# FMC_connector.net
KiCad netlist of a schematic drawn in Altium Designer
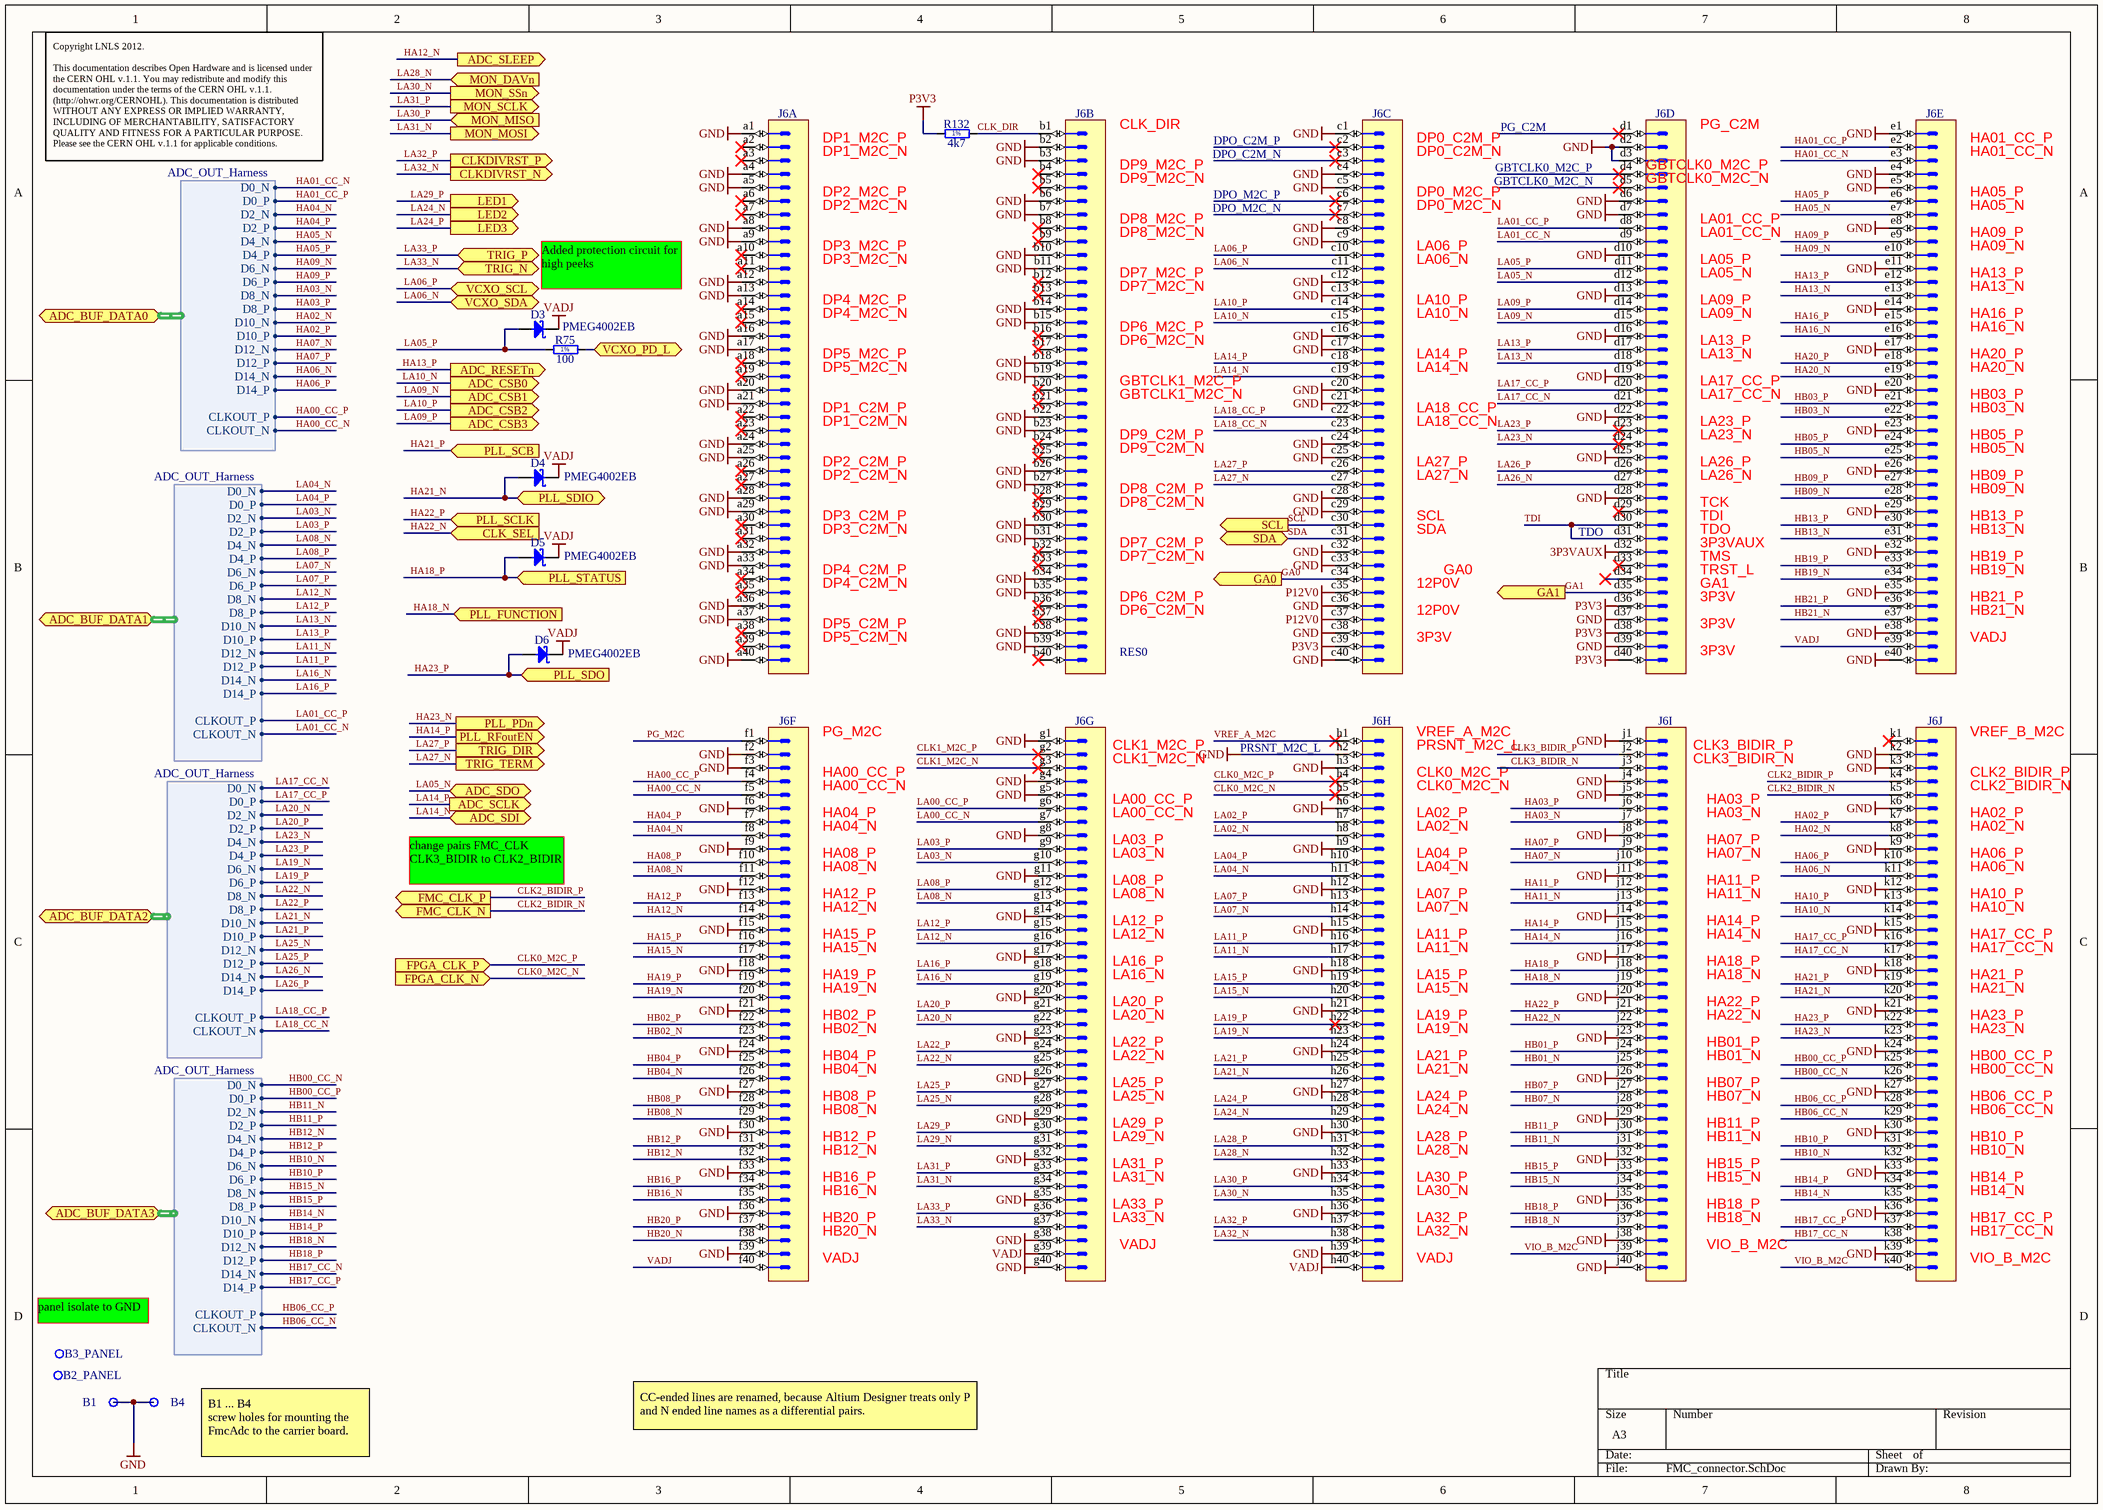
[diagram p0: FMC_connector.SchDoc]

(export (version "E")
  (design (tool "Eeschema 10.0.6"))
  (components
    (comp (ref "B1")
      (value "Plated Hole")
      (footprint "MTG270_500_M")
      (description "Single Terminal Socket")
      (fields (field (name "PART NUMBER") "PLATED_HOLE2.7_PAD5.0_M") (field (name "AUTHOR") "LNLS DIG FCS"))
      (libsource (lib "Eletro-mechanical_LNLS") (part "Single Terminal Socket"))
    )
    (comp (ref "B2_PANEL")
      (value "Plated Hole")
      (footprint "MTG270_500_M")
      (description "Single Terminal Socket")
      (fields (field (name "PART NUMBER") "PLATED_HOLE2.7_PAD5.0_M") (field (name "AUTHOR") "LNLS DIG FCS"))
      (libsource (lib "Eletro-mechanical_LNLS") (part "Single Terminal Socket"))
    )
    (comp (ref "B3_PANEL")
      (value "Plated Hole")
      (footprint "MTG270_500_M")
      (description "Single Terminal Socket")
      (fields (field (name "PART NUMBER") "PLATED_HOLE2.7_PAD5.0_M") (field (name "AUTHOR") "LNLS DIG FCS"))
      (libsource (lib "Eletro-mechanical_LNLS") (part "Single Terminal Socket"))
    )
    (comp (ref "B4")
      (value "Plated Hole")
      (footprint "MTG270_500_M")
      (description "Single Terminal Socket")
      (fields (field (name "PART NUMBER") "PLATED_HOLE2.7_PAD5.0_M") (field (name "AUTHOR") "LNLS DIG FCS"))
      (libsource (lib "Eletro-mechanical_LNLS") (part "Single Terminal Socket"))
    )
    (comp (ref "D3")
      (value "PMEG4002EB")
      (footprint "SODFL1608X65N")
      (description "Schottky Diode")
      (fields
        (field (name "VOLTAGE") "40V")
        (field (name "POWER") "200mA")
        (field (name "AUTHOR") "CERN DEM JMW")
      )
      (libsource (lib "ICs And Semiconductors") (part "Diode Schottky"))
    )
    (comp (ref "D4")
      (value "PMEG4002EB")
      (footprint "SODFL1608X65N")
      (description "Schottky Diode")
      (fields
        (field (name "VOLTAGE") "40V")
        (field (name "POWER") "200mA")
        (field (name "AUTHOR") "CERN DEM JMW")
      )
      (libsource (lib "ICs And Semiconductors") (part "Diode Schottky"))
    )
    (comp (ref "D5")
      (value "PMEG4002EB")
      (footprint "SODFL1608X65N")
      (description "Schottky Diode")
      (fields
        (field (name "VOLTAGE") "40V")
        (field (name "POWER") "200mA")
        (field (name "AUTHOR") "CERN DEM JMW")
      )
      (libsource (lib "ICs And Semiconductors") (part "Diode Schottky"))
    )
    (comp (ref "D6")
      (value "PMEG4002EB")
      (footprint "SODFL1608X65N")
      (description "Schottky Diode")
      (fields
        (field (name "VOLTAGE") "40V")
        (field (name "POWER") "200mA")
        (field (name "AUTHOR") "CERN DEM JMW")
      )
      (libsource (lib "ICs And Semiconductors") (part "Diode Schottky"))
    )
    (comp (ref "J6")
      (value "~")
      (footprint "SAMTEC_ASP-134488-01")
      (description "Connector VITA 57, 400 Male contacts in 10 row abcdefghj")
      (fields
        (field (name "PART NUMBER") "SAMTEC_ASP-134488-01")
        (field (name "MANUFACTURER") "SAMTEC")
        (field (name "AUTHOR") "CERN DEM JLC")
      )
      (libsource (lib "Connectors") (part "Connector VITA 57 400 Male (abcdefghjk)"))
    )
    (comp (ref "R75")
      (value "100")
      (footprint "RESC1005X40N")
      (description "Resistor - 1%")
      (fields
        (field (name "PART NUMBER") "R0402_100R_1%_0.0625W_100PPM")
        (field (name "POWER") "0.0625W")
        (field (name "AUTHOR") "CERN DEM JLC")
      )
      (libsource (lib "Resistors") (part "Resistor - 1%"))
    )
    (comp (ref "R132")
      (value "4k7")
      (footprint "RESC1005X40N")
      (description "Resistor - 1%")
      (fields
        (field (name "PART NUMBER") "R0402_4K7_1%_0.0625W_100PPM")
        (field (name "POWER") "0.0625W")
        (field (name "AUTHOR") "CERN DEM JLC")
      )
      (libsource (lib "Resistors") (part "Resistor - 1%"))
    )
  )
  (nets
    (net (code "2") (name "/CLK0_M2C_N") (class "Default")
      (node (ref "J6") (pin "h5") (pinfunction "h5_h5") (pintype "bidirectional+no_connect"))
    )
    (net (code "3") (name "/CLK0_M2C_P") (class "Default")
      (node (ref "J6") (pin "h4") (pinfunction "h4_h4") (pintype "bidirectional+no_connect"))
    )
    (net (code "4") (name "/CLK1_M2C_N") (class "Default")
      (node (ref "J6") (pin "g3") (pinfunction "g3_g3") (pintype "bidirectional+no_connect"))
    )
    (net (code "5") (name "/CLK1_M2C_P") (class "Default")
      (node (ref "J6") (pin "g2") (pinfunction "g2_g2") (pintype "bidirectional+no_connect"))
    )
    (net (code "6") (name "/CLK2_BIDIR_N") (class "Default")
      (node (ref "J6") (pin "k5") (pinfunction "k5_k5") (pintype "bidirectional"))
    )
    (net (code "7") (name "/CLK2_BIDIR_P") (class "Default")
      (node (ref "J6") (pin "k4") (pinfunction "k4_k4") (pintype "bidirectional"))
    )
    (net (code "8") (name "/CLK3_BIDIR_N") (class "Default")
      (node (ref "J6") (pin "j3") (pinfunction "j3_j3") (pintype "bidirectional"))
    )
    (net (code "9") (name "/CLK3_BIDIR_P") (class "Default")
      (node (ref "J6") (pin "j2") (pinfunction "j2_j2") (pintype "bidirectional"))
    )
    (net (code "10") (name "/CLK_DIR") (class "Default")
      (node (ref "J6") (pin "b1") (pinfunction "b1_b1") (pintype "bidirectional"))
      (node (ref "R132") (pin "2") (pinfunction "2_2") (pintype "passive"))
    )
    (net (code "11") (name "/GA0") (class "Default")
      (node (ref "J6") (pin "c34") (pinfunction "c34_c34") (pintype "bidirectional"))
    )
    (net (code "12") (name "/GA1") (class "Default")
      (node (ref "J6") (pin "d35") (pinfunction "d35_d35") (pintype "bidirectional"))
    )
    (net (code "13") (name "/HA00_CC_N") (class "Default")
      (node (ref "J6") (pin "f5") (pinfunction "f5_f5") (pintype "bidirectional"))
    )
    (net (code "14") (name "/HA00_CC_P") (class "Default")
      (node (ref "J6") (pin "f4") (pinfunction "f4_f4") (pintype "bidirectional"))
    )
    (net (code "15") (name "/HA01_CC_N") (class "Default")
      (node (ref "J6") (pin "e3") (pinfunction "e3_e3") (pintype "bidirectional"))
    )
    (net (code "16") (name "/HA01_CC_P") (class "Default")
      (node (ref "J6") (pin "e2") (pinfunction "e2_e2") (pintype "bidirectional"))
    )
    (net (code "17") (name "/HA02_N") (class "Default")
      (node (ref "J6") (pin "k8") (pinfunction "k8_k8") (pintype "bidirectional"))
    )
    (net (code "18") (name "/HA02_P") (class "Default")
      (node (ref "J6") (pin "k7") (pinfunction "k7_k7") (pintype "bidirectional"))
    )
    (net (code "19") (name "/HA03_N") (class "Default")
      (node (ref "J6") (pin "j7") (pinfunction "j7_j7") (pintype "bidirectional"))
    )
    (net (code "20") (name "/HA03_P") (class "Default")
      (node (ref "J6") (pin "j6") (pinfunction "j6_j6") (pintype "bidirectional"))
    )
    (net (code "21") (name "/HA04_N") (class "Default")
      (node (ref "J6") (pin "f8") (pinfunction "f8_f8") (pintype "bidirectional"))
    )
    (net (code "22") (name "/HA04_P") (class "Default")
      (node (ref "J6") (pin "f7") (pinfunction "f7_f7") (pintype "bidirectional"))
    )
    (net (code "23") (name "/HA05_N") (class "Default")
      (node (ref "J6") (pin "e7") (pinfunction "e7_e7") (pintype "bidirectional"))
    )
    (net (code "24") (name "/HA05_P") (class "Default")
      (node (ref "J6") (pin "e6") (pinfunction "e6_e6") (pintype "bidirectional"))
    )
    (net (code "25") (name "/HA06_N") (class "Default")
      (node (ref "J6") (pin "k11") (pinfunction "k11_k11") (pintype "bidirectional"))
    )
    (net (code "26") (name "/HA06_P") (class "Default")
      (node (ref "J6") (pin "k10") (pinfunction "k10_k10") (pintype "bidirectional"))
    )
    (net (code "27") (name "/HA07_N") (class "Default")
      (node (ref "J6") (pin "j10") (pinfunction "j10_j10") (pintype "bidirectional"))
    )
    (net (code "28") (name "/HA07_P") (class "Default")
      (node (ref "J6") (pin "j9") (pinfunction "j9_j9") (pintype "bidirectional"))
    )
    (net (code "29") (name "/HA08_N") (class "Default")
      (node (ref "J6") (pin "f11") (pinfunction "f11_f11") (pintype "bidirectional"))
    )
    (net (code "30") (name "/HA08_P") (class "Default")
      (node (ref "J6") (pin "f10") (pinfunction "f10_f10") (pintype "bidirectional"))
    )
    (net (code "31") (name "/HA09_N") (class "Default")
      (node (ref "J6") (pin "e10") (pinfunction "e10_e10") (pintype "bidirectional"))
    )
    (net (code "32") (name "/HA09_P") (class "Default")
      (node (ref "J6") (pin "e9") (pinfunction "e9_e9") (pintype "bidirectional"))
    )
    (net (code "33") (name "/HA10_N") (class "Default")
      (node (ref "J6") (pin "k14") (pinfunction "k14_k14") (pintype "bidirectional"))
    )
    (net (code "34") (name "/HA10_P") (class "Default")
      (node (ref "J6") (pin "k13") (pinfunction "k13_k13") (pintype "bidirectional"))
    )
    (net (code "35") (name "/HA11_N") (class "Default")
      (node (ref "J6") (pin "j13") (pinfunction "j13_j13") (pintype "bidirectional"))
    )
    (net (code "36") (name "/HA11_P") (class "Default")
      (node (ref "J6") (pin "j12") (pinfunction "j12_j12") (pintype "bidirectional"))
    )
    (net (code "37") (name "/HA12_N") (class "Default")
      (node (ref "J6") (pin "f14") (pinfunction "f14_f14") (pintype "bidirectional"))
    )
    (net (code "38") (name "/HA12_P") (class "Default")
      (node (ref "J6") (pin "f13") (pinfunction "f13_f13") (pintype "bidirectional"))
    )
    (net (code "39") (name "/HA13_N") (class "Default")
      (node (ref "J6") (pin "e13") (pinfunction "e13_e13") (pintype "bidirectional"))
    )
    (net (code "40") (name "/HA13_P") (class "Default")
      (node (ref "J6") (pin "e12") (pinfunction "e12_e12") (pintype "bidirectional"))
    )
    (net (code "41") (name "/HA14_N") (class "Default")
      (node (ref "J6") (pin "j16") (pinfunction "j16_j16") (pintype "bidirectional"))
    )
    (net (code "42") (name "/HA14_P") (class "Default")
      (node (ref "J6") (pin "j15") (pinfunction "j15_j15") (pintype "bidirectional"))
    )
    (net (code "43") (name "/HA15_N") (class "Default")
      (node (ref "J6") (pin "f17") (pinfunction "f17_f17") (pintype "bidirectional"))
    )
    (net (code "44") (name "/HA15_P") (class "Default")
      (node (ref "J6") (pin "f16") (pinfunction "f16_f16") (pintype "bidirectional"))
    )
    (net (code "45") (name "/HA16_N") (class "Default")
      (node (ref "J6") (pin "e16") (pinfunction "e16_e16") (pintype "bidirectional"))
    )
    (net (code "46") (name "/HA16_P") (class "Default")
      (node (ref "J6") (pin "e15") (pinfunction "e15_e15") (pintype "bidirectional"))
    )
    (net (code "47") (name "/HA17_CC_N") (class "Default")
      (node (ref "J6") (pin "k17") (pinfunction "k17_k17") (pintype "bidirectional"))
    )
    (net (code "48") (name "/HA17_CC_P") (class "Default")
      (node (ref "J6") (pin "k16") (pinfunction "k16_k16") (pintype "bidirectional"))
    )
    (net (code "49") (name "/HA18_N") (class "Default")
      (node (ref "J6") (pin "j19") (pinfunction "j19_j19") (pintype "bidirectional"))
    )
    (net (code "50") (name "/HA18_P") (class "Default")
      (node (ref "D5") (pin "2") (pinfunction "A_2") (pintype "passive"))
      (node (ref "J6") (pin "j18") (pinfunction "j18_j18") (pintype "bidirectional"))
    )
    (net (code "51") (name "/HA19_N") (class "Default")
      (node (ref "J6") (pin "f20") (pinfunction "f20_f20") (pintype "bidirectional"))
    )
    (net (code "52") (name "/HA19_P") (class "Default")
      (node (ref "J6") (pin "f19") (pinfunction "f19_f19") (pintype "bidirectional"))
    )
    (net (code "53") (name "/HA20_N") (class "Default")
      (node (ref "J6") (pin "e19") (pinfunction "e19_e19") (pintype "bidirectional"))
    )
    (net (code "54") (name "/HA20_P") (class "Default")
      (node (ref "J6") (pin "e18") (pinfunction "e18_e18") (pintype "bidirectional"))
    )
    (net (code "55") (name "/HA21_N") (class "Default")
      (node (ref "D4") (pin "2") (pinfunction "A_2") (pintype "passive"))
      (node (ref "J6") (pin "k20") (pinfunction "k20_k20") (pintype "bidirectional"))
    )
    (net (code "56") (name "/HA21_P") (class "Default")
      (node (ref "J6") (pin "k19") (pinfunction "k19_k19") (pintype "bidirectional"))
    )
    (net (code "57") (name "/HA22_N") (class "Default")
      (node (ref "J6") (pin "j22") (pinfunction "j22_j22") (pintype "bidirectional"))
    )
    (net (code "58") (name "/HA22_P") (class "Default")
      (node (ref "J6") (pin "j21") (pinfunction "j21_j21") (pintype "bidirectional"))
    )
    (net (code "59") (name "/HA23_N") (class "Default")
      (node (ref "J6") (pin "k23") (pinfunction "k23_k23") (pintype "bidirectional"))
    )
    (net (code "60") (name "/HA23_P") (class "Default")
      (node (ref "D6") (pin "2") (pinfunction "A_2") (pintype "passive"))
      (node (ref "J6") (pin "k22") (pinfunction "k22_k22") (pintype "bidirectional"))
    )
    (net (code "61") (name "/HB00_CC_N") (class "Default")
      (node (ref "J6") (pin "k26") (pinfunction "k26_k26") (pintype "bidirectional"))
    )
    (net (code "62") (name "/HB00_CC_P") (class "Default")
      (node (ref "J6") (pin "k25") (pinfunction "k25_k25") (pintype "bidirectional"))
    )
    (net (code "63") (name "/HB01_N") (class "Default")
      (node (ref "J6") (pin "j25") (pinfunction "j25_j25") (pintype "bidirectional"))
    )
    (net (code "64") (name "/HB01_P") (class "Default")
      (node (ref "J6") (pin "j24") (pinfunction "j24_j24") (pintype "bidirectional"))
    )
    (net (code "65") (name "/HB02_N") (class "Default")
      (node (ref "J6") (pin "f23") (pinfunction "f23_f23") (pintype "bidirectional"))
    )
    (net (code "66") (name "/HB02_P") (class "Default")
      (node (ref "J6") (pin "f22") (pinfunction "f22_f22") (pintype "bidirectional"))
    )
    (net (code "67") (name "/HB03_N") (class "Default")
      (node (ref "J6") (pin "e22") (pinfunction "e22_e22") (pintype "bidirectional"))
    )
    (net (code "68") (name "/HB03_P") (class "Default")
      (node (ref "J6") (pin "e21") (pinfunction "e21_e21") (pintype "bidirectional"))
    )
    (net (code "69") (name "/HB04_N") (class "Default")
      (node (ref "J6") (pin "f26") (pinfunction "f26_f26") (pintype "bidirectional"))
    )
    (net (code "70") (name "/HB04_P") (class "Default")
      (node (ref "J6") (pin "f25") (pinfunction "f25_f25") (pintype "bidirectional"))
    )
    (net (code "71") (name "/HB05_N") (class "Default")
      (node (ref "J6") (pin "e25") (pinfunction "e25_e25") (pintype "bidirectional"))
    )
    (net (code "72") (name "/HB05_P") (class "Default")
      (node (ref "J6") (pin "e24") (pinfunction "e24_e24") (pintype "bidirectional"))
    )
    (net (code "73") (name "/HB06_CC_N") (class "Default")
      (node (ref "J6") (pin "k29") (pinfunction "k29_k29") (pintype "bidirectional"))
    )
    (net (code "74") (name "/HB06_CC_P") (class "Default")
      (node (ref "J6") (pin "k28") (pinfunction "k28_k28") (pintype "bidirectional"))
    )
    (net (code "75") (name "/HB07_N") (class "Default")
      (node (ref "J6") (pin "j28") (pinfunction "j28_j28") (pintype "bidirectional"))
    )
    (net (code "76") (name "/HB07_P") (class "Default")
      (node (ref "J6") (pin "j27") (pinfunction "j27_j27") (pintype "bidirectional"))
    )
    (net (code "77") (name "/HB08_N") (class "Default")
      (node (ref "J6") (pin "f29") (pinfunction "f29_f29") (pintype "bidirectional"))
    )
    (net (code "78") (name "/HB08_P") (class "Default")
      (node (ref "J6") (pin "f28") (pinfunction "f28_f28") (pintype "bidirectional"))
    )
    (net (code "79") (name "/HB09_N") (class "Default")
      (node (ref "J6") (pin "e28") (pinfunction "e28_e28") (pintype "bidirectional"))
    )
    (net (code "80") (name "/HB09_P") (class "Default")
      (node (ref "J6") (pin "e27") (pinfunction "e27_e27") (pintype "bidirectional"))
    )
    (net (code "81") (name "/HB10_N") (class "Default")
      (node (ref "J6") (pin "k32") (pinfunction "k32_k32") (pintype "bidirectional"))
    )
    (net (code "82") (name "/HB10_P") (class "Default")
      (node (ref "J6") (pin "k31") (pinfunction "k31_k31") (pintype "bidirectional"))
    )
    (net (code "83") (name "/HB11_N") (class "Default")
      (node (ref "J6") (pin "j31") (pinfunction "j31_j31") (pintype "bidirectional"))
    )
    (net (code "84") (name "/HB11_P") (class "Default")
      (node (ref "J6") (pin "j30") (pinfunction "j30_j30") (pintype "bidirectional"))
    )
    (net (code "85") (name "/HB12_N") (class "Default")
      (node (ref "J6") (pin "f32") (pinfunction "f32_f32") (pintype "bidirectional"))
    )
    (net (code "86") (name "/HB12_P") (class "Default")
      (node (ref "J6") (pin "f31") (pinfunction "f31_f31") (pintype "bidirectional"))
    )
    (net (code "87") (name "/HB13_N") (class "Default")
      (node (ref "J6") (pin "e31") (pinfunction "e31_e31") (pintype "bidirectional"))
    )
    (net (code "88") (name "/HB13_P") (class "Default")
      (node (ref "J6") (pin "e30") (pinfunction "e30_e30") (pintype "bidirectional"))
    )
    (net (code "89") (name "/HB14_N") (class "Default")
      (node (ref "J6") (pin "k35") (pinfunction "k35_k35") (pintype "bidirectional"))
    )
    (net (code "90") (name "/HB14_P") (class "Default")
      (node (ref "J6") (pin "k34") (pinfunction "k34_k34") (pintype "bidirectional"))
    )
    (net (code "91") (name "/HB15_N") (class "Default")
      (node (ref "J6") (pin "j34") (pinfunction "j34_j34") (pintype "bidirectional"))
    )
    (net (code "92") (name "/HB15_P") (class "Default")
      (node (ref "J6") (pin "j33") (pinfunction "j33_j33") (pintype "bidirectional"))
    )
    (net (code "93") (name "/HB16_N") (class "Default")
      (node (ref "J6") (pin "f35") (pinfunction "f35_f35") (pintype "bidirectional"))
    )
    (net (code "94") (name "/HB16_P") (class "Default")
      (node (ref "J6") (pin "f34") (pinfunction "f34_f34") (pintype "bidirectional"))
    )
    (net (code "95") (name "/HB17_CC_N") (class "Default")
      (node (ref "J6") (pin "k38") (pinfunction "k38_k38") (pintype "bidirectional"))
    )
    (net (code "96") (name "/HB17_CC_P") (class "Default")
      (node (ref "J6") (pin "k37") (pinfunction "k37_k37") (pintype "bidirectional"))
    )
    (net (code "97") (name "/HB18_N") (class "Default")
      (node (ref "J6") (pin "j37") (pinfunction "j37_j37") (pintype "bidirectional"))
    )
    (net (code "98") (name "/HB18_P") (class "Default")
      (node (ref "J6") (pin "j36") (pinfunction "j36_j36") (pintype "bidirectional"))
    )
    (net (code "99") (name "/HB19_N") (class "Default")
      (node (ref "J6") (pin "e34") (pinfunction "e34_e34") (pintype "bidirectional"))
    )
    (net (code "100") (name "/HB19_P") (class "Default")
      (node (ref "J6") (pin "e33") (pinfunction "e33_e33") (pintype "bidirectional"))
    )
    (net (code "101") (name "/HB20_N") (class "Default")
      (node (ref "J6") (pin "f38") (pinfunction "f38_f38") (pintype "bidirectional"))
    )
    (net (code "102") (name "/HB20_P") (class "Default")
      (node (ref "J6") (pin "f37") (pinfunction "f37_f37") (pintype "bidirectional"))
    )
    (net (code "103") (name "/HB21_N") (class "Default")
      (node (ref "J6") (pin "e37") (pinfunction "e37_e37") (pintype "bidirectional"))
    )
    (net (code "104") (name "/HB21_P") (class "Default")
      (node (ref "J6") (pin "e36") (pinfunction "e36_e36") (pintype "bidirectional"))
    )
    (net (code "105") (name "/LA00_CC_N") (class "Default")
      (node (ref "J6") (pin "g7") (pinfunction "g7_g7") (pintype "bidirectional"))
    )
    (net (code "106") (name "/LA00_CC_P") (class "Default")
      (node (ref "J6") (pin "g6") (pinfunction "g6_g6") (pintype "bidirectional"))
    )
    (net (code "107") (name "/LA01_CC_N") (class "Default")
      (node (ref "J6") (pin "d9") (pinfunction "d9_d9") (pintype "bidirectional"))
    )
    (net (code "108") (name "/LA01_CC_P") (class "Default")
      (node (ref "J6") (pin "d8") (pinfunction "d8_d8") (pintype "bidirectional"))
    )
    (net (code "109") (name "/LA02_N") (class "Default")
      (node (ref "J6") (pin "h8") (pinfunction "h8_h8") (pintype "bidirectional"))
    )
    (net (code "110") (name "/LA02_P") (class "Default")
      (node (ref "J6") (pin "h7") (pinfunction "h7_h7") (pintype "bidirectional"))
    )
    (net (code "111") (name "/LA03_N") (class "Default")
      (node (ref "J6") (pin "g10") (pinfunction "g10_g10") (pintype "bidirectional"))
    )
    (net (code "112") (name "/LA03_P") (class "Default")
      (node (ref "J6") (pin "g9") (pinfunction "g9_g9") (pintype "bidirectional"))
    )
    (net (code "113") (name "/LA04_N") (class "Default")
      (node (ref "J6") (pin "h11") (pinfunction "h11_h11") (pintype "bidirectional"))
    )
    (net (code "114") (name "/LA04_P") (class "Default")
      (node (ref "J6") (pin "h10") (pinfunction "h10_h10") (pintype "bidirectional"))
    )
    (net (code "115") (name "/LA05_N") (class "Default")
      (node (ref "J6") (pin "d12") (pinfunction "d12_d12") (pintype "bidirectional"))
    )
    (net (code "116") (name "/LA05_P") (class "Default")
      (node (ref "D3") (pin "2") (pinfunction "A_2") (pintype "passive"))
      (node (ref "J6") (pin "d11") (pinfunction "d11_d11") (pintype "bidirectional"))
      (node (ref "R75") (pin "1") (pinfunction "1_1") (pintype "passive"))
    )
    (net (code "117") (name "/LA06_N") (class "Default")
      (node (ref "J6") (pin "c11") (pinfunction "c11_c11") (pintype "bidirectional"))
    )
    (net (code "118") (name "/LA06_P") (class "Default")
      (node (ref "J6") (pin "c10") (pinfunction "c10_c10") (pintype "bidirectional"))
    )
    (net (code "119") (name "/LA07_N") (class "Default")
      (node (ref "J6") (pin "h14") (pinfunction "h14_h14") (pintype "bidirectional"))
    )
    (net (code "120") (name "/LA07_P") (class "Default")
      (node (ref "J6") (pin "h13") (pinfunction "h13_h13") (pintype "bidirectional"))
    )
    (net (code "121") (name "/LA08_N") (class "Default")
      (node (ref "J6") (pin "g13") (pinfunction "g13_g13") (pintype "bidirectional"))
    )
    (net (code "122") (name "/LA08_P") (class "Default")
      (node (ref "J6") (pin "g12") (pinfunction "g12_g12") (pintype "bidirectional"))
    )
    (net (code "123") (name "/LA09_N") (class "Default")
      (node (ref "J6") (pin "d15") (pinfunction "d15_d15") (pintype "bidirectional"))
    )
    (net (code "124") (name "/LA09_P") (class "Default")
      (node (ref "J6") (pin "d14") (pinfunction "d14_d14") (pintype "bidirectional"))
    )
    (net (code "125") (name "/LA10_N") (class "Default")
      (node (ref "J6") (pin "c15") (pinfunction "c15_c15") (pintype "bidirectional"))
    )
    (net (code "126") (name "/LA10_P") (class "Default")
      (node (ref "J6") (pin "c14") (pinfunction "c14_c14") (pintype "bidirectional"))
    )
    (net (code "127") (name "/LA11_N") (class "Default")
      (node (ref "J6") (pin "h17") (pinfunction "h17_h17") (pintype "bidirectional"))
    )
    (net (code "128") (name "/LA11_P") (class "Default")
      (node (ref "J6") (pin "h16") (pinfunction "h16_h16") (pintype "bidirectional"))
    )
    (net (code "129") (name "/LA12_N") (class "Default")
      (node (ref "J6") (pin "g16") (pinfunction "g16_g16") (pintype "bidirectional"))
    )
    (net (code "130") (name "/LA12_P") (class "Default")
      (node (ref "J6") (pin "g15") (pinfunction "g15_g15") (pintype "bidirectional"))
    )
    (net (code "131") (name "/LA13_N") (class "Default")
      (node (ref "J6") (pin "d18") (pinfunction "d18_d18") (pintype "bidirectional"))
    )
    (net (code "132") (name "/LA13_P") (class "Default")
      (node (ref "J6") (pin "d17") (pinfunction "d17_d17") (pintype "bidirectional"))
    )
    (net (code "133") (name "/LA14_N") (class "Default")
      (node (ref "J6") (pin "c19") (pinfunction "c19_c19") (pintype "bidirectional"))
    )
    (net (code "134") (name "/LA14_P") (class "Default")
      (node (ref "J6") (pin "c18") (pinfunction "c18_c18") (pintype "bidirectional"))
    )
    (net (code "135") (name "/LA15_N") (class "Default")
      (node (ref "J6") (pin "h20") (pinfunction "h20_h20") (pintype "bidirectional"))
    )
    (net (code "136") (name "/LA15_P") (class "Default")
      (node (ref "J6") (pin "h19") (pinfunction "h19_h19") (pintype "bidirectional"))
    )
    (net (code "137") (name "/LA16_N") (class "Default")
      (node (ref "J6") (pin "g19") (pinfunction "g19_g19") (pintype "bidirectional"))
    )
    (net (code "138") (name "/LA16_P") (class "Default")
      (node (ref "J6") (pin "g18") (pinfunction "g18_g18") (pintype "bidirectional"))
    )
    (net (code "139") (name "/LA17_CC_N") (class "Default")
      (node (ref "J6") (pin "d21") (pinfunction "d21_d21") (pintype "bidirectional"))
    )
    (net (code "140") (name "/LA17_CC_P") (class "Default")
      (node (ref "J6") (pin "d20") (pinfunction "d20_d20") (pintype "bidirectional"))
    )
    (net (code "141") (name "/LA18_CC_N") (class "Default")
      (node (ref "J6") (pin "c23") (pinfunction "c23_c23") (pintype "bidirectional"))
    )
    (net (code "142") (name "/LA18_CC_P") (class "Default")
      (node (ref "J6") (pin "c22") (pinfunction "c22_c22") (pintype "bidirectional"))
    )
    (net (code "143") (name "/LA19_N") (class "Default")
      (node (ref "J6") (pin "h23") (pinfunction "h23_h23") (pintype "bidirectional"))
    )
    (net (code "144") (name "/LA19_P") (class "Default")
      (node (ref "J6") (pin "h22") (pinfunction "h22_h22") (pintype "bidirectional+no_connect"))
    )
    (net (code "145") (name "/LA20_N") (class "Default")
      (node (ref "J6") (pin "g22") (pinfunction "g22_g22") (pintype "bidirectional"))
    )
    (net (code "146") (name "/LA20_P") (class "Default")
      (node (ref "J6") (pin "g21") (pinfunction "g21_g21") (pintype "bidirectional"))
    )
    (net (code "147") (name "/LA21_N") (class "Default")
      (node (ref "J6") (pin "h26") (pinfunction "h26_h26") (pintype "bidirectional"))
    )
    (net (code "148") (name "/LA21_P") (class "Default")
      (node (ref "J6") (pin "h25") (pinfunction "h25_h25") (pintype "bidirectional"))
    )
    (net (code "149") (name "/LA22_N") (class "Default")
      (node (ref "J6") (pin "g25") (pinfunction "g25_g25") (pintype "bidirectional"))
    )
    (net (code "150") (name "/LA22_P") (class "Default")
      (node (ref "J6") (pin "g24") (pinfunction "g24_g24") (pintype "bidirectional"))
    )
    (net (code "151") (name "/LA23_N") (class "Default")
      (node (ref "J6") (pin "d24") (pinfunction "d24_d24") (pintype "bidirectional"))
    )
    (net (code "152") (name "/LA23_P") (class "Default")
      (node (ref "J6") (pin "d23") (pinfunction "d23_d23") (pintype "bidirectional"))
    )
    (net (code "153") (name "/LA24_N") (class "Default")
      (node (ref "J6") (pin "h29") (pinfunction "h29_h29") (pintype "bidirectional"))
    )
    (net (code "154") (name "/LA24_P") (class "Default")
      (node (ref "J6") (pin "h28") (pinfunction "h28_h28") (pintype "bidirectional"))
    )
    (net (code "155") (name "/LA25_N") (class "Default")
      (node (ref "J6") (pin "g28") (pinfunction "g28_g28") (pintype "bidirectional"))
    )
    (net (code "156") (name "/LA25_P") (class "Default")
      (node (ref "J6") (pin "g27") (pinfunction "g27_g27") (pintype "bidirectional"))
    )
    (net (code "157") (name "/LA26_N") (class "Default")
      (node (ref "J6") (pin "d27") (pinfunction "d27_d27") (pintype "bidirectional"))
    )
    (net (code "158") (name "/LA26_P") (class "Default")
      (node (ref "J6") (pin "d26") (pinfunction "d26_d26") (pintype "bidirectional"))
    )
    (net (code "159") (name "/LA27_N") (class "Default")
      (node (ref "J6") (pin "c27") (pinfunction "c27_c27") (pintype "bidirectional"))
    )
    (net (code "160") (name "/LA27_P") (class "Default")
      (node (ref "J6") (pin "c26") (pinfunction "c26_c26") (pintype "bidirectional"))
    )
    (net (code "161") (name "/LA28_N") (class "Default")
      (node (ref "J6") (pin "h32") (pinfunction "h32_h32") (pintype "bidirectional"))
    )
    (net (code "162") (name "/LA28_P") (class "Default")
      (node (ref "J6") (pin "h31") (pinfunction "h31_h31") (pintype "bidirectional"))
    )
    (net (code "163") (name "/LA29_N") (class "Default")
      (node (ref "J6") (pin "g31") (pinfunction "g31_g31") (pintype "bidirectional"))
    )
    (net (code "164") (name "/LA29_P") (class "Default")
      (node (ref "J6") (pin "g30") (pinfunction "g30_g30") (pintype "bidirectional"))
    )
    (net (code "165") (name "/LA30_N") (class "Default")
      (node (ref "J6") (pin "h35") (pinfunction "h35_h35") (pintype "bidirectional"))
    )
    (net (code "166") (name "/LA30_P") (class "Default")
      (node (ref "J6") (pin "h34") (pinfunction "h34_h34") (pintype "bidirectional"))
    )
    (net (code "167") (name "/LA31_N") (class "Default")
      (node (ref "J6") (pin "g34") (pinfunction "g34_g34") (pintype "bidirectional"))
    )
    (net (code "168") (name "/LA31_P") (class "Default")
      (node (ref "J6") (pin "g33") (pinfunction "g33_g33") (pintype "bidirectional"))
    )
    (net (code "169") (name "/LA32_N") (class "Default")
      (node (ref "J6") (pin "h38") (pinfunction "h38_h38") (pintype "bidirectional"))
    )
    (net (code "170") (name "/LA32_P") (class "Default")
      (node (ref "J6") (pin "h37") (pinfunction "h37_h37") (pintype "bidirectional"))
    )
    (net (code "171") (name "/LA33_N") (class "Default")
      (node (ref "J6") (pin "g37") (pinfunction "g37_g37") (pintype "bidirectional"))
    )
    (net (code "172") (name "/LA33_P") (class "Default")
      (node (ref "J6") (pin "g36") (pinfunction "g36_g36") (pintype "bidirectional"))
    )
    (net (code "173") (name "/PG_M2C") (class "Default")
      (node (ref "J6") (pin "f1") (pinfunction "f1_f1") (pintype "bidirectional"))
    )
    (net (code "174") (name "/SCL") (class "Default")
      (node (ref "J6") (pin "c30") (pinfunction "c30_c30") (pintype "bidirectional"))
    )
    (net (code "175") (name "/SDA") (class "Default")
      (node (ref "J6") (pin "c31") (pinfunction "c31_c31") (pintype "bidirectional"))
    )
    (net (code "176") (name "/TDI") (class "Default")
      (node (ref "J6") (pin "d30") (pinfunction "d30_d30") (pintype "bidirectional"))
      (node (ref "J6") (pin "d31") (pinfunction "d31_d31") (pintype "bidirectional"))
    )
    (net (code "177") (name "/VCXO_PD_L") (class "Default")
      (node (ref "R75") (pin "2") (pinfunction "2_2") (pintype "passive"))
    )
    (net (code "178") (name "/VIO_B_M2C") (class "Default")
      (node (ref "J6") (pin "j39") (pinfunction "j39_j39") (pintype "bidirectional"))
      (node (ref "J6") (pin "k40") (pinfunction "k40_k40") (pintype "bidirectional"))
    )
    (net (code "179") (name "/VREF_A_M2C") (class "Default")
      (node (ref "J6") (pin "h1") (pinfunction "h1_h1") (pintype "bidirectional+no_connect"))
    )
    (net (code "181") (name "3P3VAUX") (class "Default")
      (node (ref "J6") (pin "d32") (pinfunction "d32_d32") (pintype "bidirectional"))
    )
    (net (code "182") (name "GND") (class "Default")
      (node (ref "B1") (pin "1") (pinfunction "1_1") (pintype "bidirectional"))
      (node (ref "B4") (pin "1") (pinfunction "1_1") (pintype "bidirectional"))
      (node (ref "J6") (pin "a1") (pinfunction "a1_a1") (pintype "bidirectional"))
      (node (ref "J6") (pin "a12") (pinfunction "a12_a12") (pintype "bidirectional"))
      (node (ref "J6") (pin "a13") (pinfunction "a13_a13") (pintype "bidirectional"))
      (node (ref "J6") (pin "a16") (pinfunction "a16_a16") (pintype "bidirectional"))
      (node (ref "J6") (pin "a17") (pinfunction "a17_a17") (pintype "bidirectional"))
      (node (ref "J6") (pin "a20") (pinfunction "a20_a20") (pintype "bidirectional"))
      (node (ref "J6") (pin "a21") (pinfunction "a21_a21") (pintype "bidirectional"))
      (node (ref "J6") (pin "a24") (pinfunction "a24_a24") (pintype "bidirectional"))
      (node (ref "J6") (pin "a25") (pinfunction "a25_a25") (pintype "bidirectional"))
      (node (ref "J6") (pin "a28") (pinfunction "a28_a28") (pintype "bidirectional"))
      (node (ref "J6") (pin "a29") (pinfunction "a29_a29") (pintype "bidirectional"))
      (node (ref "J6") (pin "a32") (pinfunction "a32_a32") (pintype "bidirectional"))
      (node (ref "J6") (pin "a33") (pinfunction "a33_a33") (pintype "bidirectional"))
      (node (ref "J6") (pin "a36") (pinfunction "a36_a36") (pintype "bidirectional"))
      (node (ref "J6") (pin "a37") (pinfunction "a37_a37") (pintype "bidirectional"))
      (node (ref "J6") (pin "a4") (pinfunction "a4_a4") (pintype "bidirectional"))
      (node (ref "J6") (pin "a40") (pinfunction "a40_a40") (pintype "bidirectional"))
      (node (ref "J6") (pin "a5") (pinfunction "a5_a5") (pintype "bidirectional"))
      (node (ref "J6") (pin "a8") (pinfunction "a8_a8") (pintype "bidirectional"))
      (node (ref "J6") (pin "a9") (pinfunction "a9_a9") (pintype "bidirectional"))
      (node (ref "J6") (pin "b10") (pinfunction "b10_b10") (pintype "bidirectional"))
      (node (ref "J6") (pin "b11") (pinfunction "b11_b11") (pintype "bidirectional"))
      (node (ref "J6") (pin "b14") (pinfunction "b14_b14") (pintype "bidirectional"))
      (node (ref "J6") (pin "b15") (pinfunction "b15_b15") (pintype "bidirectional"))
      (node (ref "J6") (pin "b18") (pinfunction "b18_b18") (pintype "bidirectional"))
      (node (ref "J6") (pin "b19") (pinfunction "b19_b19") (pintype "bidirectional"))
      (node (ref "J6") (pin "b2") (pinfunction "b2_b2") (pintype "bidirectional"))
      (node (ref "J6") (pin "b22") (pinfunction "b22_b22") (pintype "bidirectional"))
      (node (ref "J6") (pin "b23") (pinfunction "b23_b23") (pintype "bidirectional"))
      (node (ref "J6") (pin "b26") (pinfunction "b26_b26") (pintype "bidirectional"))
      (node (ref "J6") (pin "b27") (pinfunction "b27_b27") (pintype "bidirectional"))
      (node (ref "J6") (pin "b3") (pinfunction "b3_b3") (pintype "bidirectional"))
      (node (ref "J6") (pin "b30") (pinfunction "b30_b30") (pintype "bidirectional"))
      (node (ref "J6") (pin "b31") (pinfunction "b31_b31") (pintype "bidirectional"))
      (node (ref "J6") (pin "b34") (pinfunction "b34_b34") (pintype "bidirectional"))
      (node (ref "J6") (pin "b35") (pinfunction "b35_b35") (pintype "bidirectional"))
      (node (ref "J6") (pin "b38") (pinfunction "b38_b38") (pintype "bidirectional"))
      (node (ref "J6") (pin "b39") (pinfunction "b39_b39") (pintype "bidirectional"))
      (node (ref "J6") (pin "b6") (pinfunction "b6_b6") (pintype "bidirectional"))
      (node (ref "J6") (pin "b7") (pinfunction "b7_b7") (pintype "bidirectional"))
      (node (ref "J6") (pin "c1") (pinfunction "c1_c1") (pintype "bidirectional"))
      (node (ref "J6") (pin "c12") (pinfunction "c12_c12") (pintype "bidirectional"))
      (node (ref "J6") (pin "c13") (pinfunction "c13_c13") (pintype "bidirectional"))
      (node (ref "J6") (pin "c16") (pinfunction "c16_c16") (pintype "bidirectional"))
      (node (ref "J6") (pin "c17") (pinfunction "c17_c17") (pintype "bidirectional"))
      (node (ref "J6") (pin "c20") (pinfunction "c20_c20") (pintype "bidirectional"))
      (node (ref "J6") (pin "c21") (pinfunction "c21_c21") (pintype "bidirectional"))
      (node (ref "J6") (pin "c24") (pinfunction "c24_c24") (pintype "bidirectional"))
      (node (ref "J6") (pin "c25") (pinfunction "c25_c25") (pintype "bidirectional"))
      (node (ref "J6") (pin "c28") (pinfunction "c28_c28") (pintype "bidirectional"))
      (node (ref "J6") (pin "c29") (pinfunction "c29_c29") (pintype "bidirectional"))
      (node (ref "J6") (pin "c32") (pinfunction "c32_c32") (pintype "bidirectional"))
      (node (ref "J6") (pin "c33") (pinfunction "c33_c33") (pintype "bidirectional"))
      (node (ref "J6") (pin "c36") (pinfunction "c36_c36") (pintype "bidirectional"))
      (node (ref "J6") (pin "c38") (pinfunction "c38_c38") (pintype "bidirectional"))
      (node (ref "J6") (pin "c4") (pinfunction "c4_c4") (pintype "bidirectional"))
      (node (ref "J6") (pin "c40") (pinfunction "c40_c40") (pintype "bidirectional"))
      (node (ref "J6") (pin "c5") (pinfunction "c5_c5") (pintype "bidirectional"))
      (node (ref "J6") (pin "c8") (pinfunction "c8_c8") (pintype "bidirectional"))
      (node (ref "J6") (pin "c9") (pinfunction "c9_c9") (pintype "bidirectional"))
      (node (ref "J6") (pin "d10") (pinfunction "d10_d10") (pintype "bidirectional"))
      (node (ref "J6") (pin "d13") (pinfunction "d13_d13") (pintype "bidirectional"))
      (node (ref "J6") (pin "d16") (pinfunction "d16_d16") (pintype "bidirectional"))
      (node (ref "J6") (pin "d19") (pinfunction "d19_d19") (pintype "bidirectional"))
      (node (ref "J6") (pin "d2") (pinfunction "d2_d2") (pintype "bidirectional"))
      (node (ref "J6") (pin "d22") (pinfunction "d22_d22") (pintype "bidirectional"))
      (node (ref "J6") (pin "d25") (pinfunction "d25_d25") (pintype "bidirectional"))
      (node (ref "J6") (pin "d28") (pinfunction "d28_d28") (pintype "bidirectional"))
      (node (ref "J6") (pin "d3") (pinfunction "d3_d3") (pintype "bidirectional"))
      (node (ref "J6") (pin "d37") (pinfunction "d37_d37") (pintype "bidirectional"))
      (node (ref "J6") (pin "d39") (pinfunction "d39_d39") (pintype "bidirectional"))
      (node (ref "J6") (pin "d6") (pinfunction "d6_d6") (pintype "bidirectional"))
      (node (ref "J6") (pin "d7") (pinfunction "d7_d7") (pintype "bidirectional"))
      (node (ref "J6") (pin "e1") (pinfunction "e1_e1") (pintype "bidirectional"))
      (node (ref "J6") (pin "e11") (pinfunction "e11_e11") (pintype "bidirectional"))
      (node (ref "J6") (pin "e14") (pinfunction "e14_e14") (pintype "bidirectional"))
      (node (ref "J6") (pin "e17") (pinfunction "e17_e17") (pintype "bidirectional"))
      (node (ref "J6") (pin "e20") (pinfunction "e20_e20") (pintype "bidirectional"))
      (node (ref "J6") (pin "e23") (pinfunction "e23_e23") (pintype "bidirectional"))
      (node (ref "J6") (pin "e26") (pinfunction "e26_e26") (pintype "bidirectional"))
      (node (ref "J6") (pin "e29") (pinfunction "e29_e29") (pintype "bidirectional"))
      (node (ref "J6") (pin "e32") (pinfunction "e32_e32") (pintype "bidirectional"))
      (node (ref "J6") (pin "e35") (pinfunction "e35_e35") (pintype "bidirectional"))
      (node (ref "J6") (pin "e38") (pinfunction "e38_e38") (pintype "bidirectional"))
      (node (ref "J6") (pin "e4") (pinfunction "e4_e4") (pintype "bidirectional"))
      (node (ref "J6") (pin "e40") (pinfunction "e40_e40") (pintype "bidirectional"))
      (node (ref "J6") (pin "e5") (pinfunction "e5_e5") (pintype "bidirectional"))
      (node (ref "J6") (pin "e8") (pinfunction "e8_e8") (pintype "bidirectional"))
      (node (ref "J6") (pin "f12") (pinfunction "f12_f12") (pintype "bidirectional"))
      (node (ref "J6") (pin "f15") (pinfunction "f15_f15") (pintype "bidirectional"))
      (node (ref "J6") (pin "f18") (pinfunction "f18_f18") (pintype "bidirectional"))
      (node (ref "J6") (pin "f2") (pinfunction "f2_f2") (pintype "bidirectional"))
      (node (ref "J6") (pin "f21") (pinfunction "f21_f21") (pintype "bidirectional"))
      (node (ref "J6") (pin "f24") (pinfunction "f24_f24") (pintype "bidirectional"))
      (node (ref "J6") (pin "f27") (pinfunction "f27_f27") (pintype "bidirectional"))
      (node (ref "J6") (pin "f3") (pinfunction "f3_f3") (pintype "bidirectional"))
      (node (ref "J6") (pin "f30") (pinfunction "f30_f30") (pintype "bidirectional"))
      (node (ref "J6") (pin "f33") (pinfunction "f33_f33") (pintype "bidirectional"))
      (node (ref "J6") (pin "f36") (pinfunction "f36_f36") (pintype "bidirectional"))
      (node (ref "J6") (pin "f39") (pinfunction "f39_f39") (pintype "bidirectional"))
      (node (ref "J6") (pin "f6") (pinfunction "f6_f6") (pintype "bidirectional"))
      (node (ref "J6") (pin "f9") (pinfunction "f9_f9") (pintype "bidirectional"))
      (node (ref "J6") (pin "g1") (pinfunction "g1_g1") (pintype "bidirectional"))
      (node (ref "J6") (pin "g11") (pinfunction "g11_g11") (pintype "bidirectional"))
      (node (ref "J6") (pin "g14") (pinfunction "g14_g14") (pintype "bidirectional"))
      (node (ref "J6") (pin "g17") (pinfunction "g17_g17") (pintype "bidirectional"))
      (node (ref "J6") (pin "g20") (pinfunction "g20_g20") (pintype "bidirectional"))
      (node (ref "J6") (pin "g23") (pinfunction "g23_g23") (pintype "bidirectional"))
      (node (ref "J6") (pin "g26") (pinfunction "g26_g26") (pintype "bidirectional"))
      (node (ref "J6") (pin "g29") (pinfunction "g29_g29") (pintype "bidirectional"))
      (node (ref "J6") (pin "g32") (pinfunction "g32_g32") (pintype "bidirectional"))
      (node (ref "J6") (pin "g35") (pinfunction "g35_g35") (pintype "bidirectional"))
      (node (ref "J6") (pin "g38") (pinfunction "g38_g38") (pintype "bidirectional"))
      (node (ref "J6") (pin "g4") (pinfunction "g4_g4") (pintype "bidirectional"))
      (node (ref "J6") (pin "g40") (pinfunction "g40_g40") (pintype "bidirectional"))
      (node (ref "J6") (pin "g5") (pinfunction "g5_g5") (pintype "bidirectional"))
      (node (ref "J6") (pin "g8") (pinfunction "g8_g8") (pintype "bidirectional"))
      (node (ref "J6") (pin "h12") (pinfunction "h12_h12") (pintype "bidirectional"))
      (node (ref "J6") (pin "h15") (pinfunction "h15_h15") (pintype "bidirectional"))
      (node (ref "J6") (pin "h18") (pinfunction "h18_h18") (pintype "bidirectional"))
      (node (ref "J6") (pin "h2") (pinfunction "h2_h2") (pintype "bidirectional"))
      (node (ref "J6") (pin "h21") (pinfunction "h21_h21") (pintype "bidirectional"))
      (node (ref "J6") (pin "h24") (pinfunction "h24_h24") (pintype "bidirectional"))
      (node (ref "J6") (pin "h27") (pinfunction "h27_h27") (pintype "bidirectional"))
      (node (ref "J6") (pin "h3") (pinfunction "h3_h3") (pintype "bidirectional"))
      (node (ref "J6") (pin "h30") (pinfunction "h30_h30") (pintype "bidirectional"))
      (node (ref "J6") (pin "h33") (pinfunction "h33_h33") (pintype "bidirectional"))
      (node (ref "J6") (pin "h36") (pinfunction "h36_h36") (pintype "bidirectional"))
      (node (ref "J6") (pin "h39") (pinfunction "h39_h39") (pintype "bidirectional"))
      (node (ref "J6") (pin "h6") (pinfunction "h6_h6") (pintype "bidirectional"))
      (node (ref "J6") (pin "h9") (pinfunction "h9_h9") (pintype "bidirectional"))
      (node (ref "J6") (pin "j1") (pinfunction "j1_j1") (pintype "bidirectional"))
      (node (ref "J6") (pin "j11") (pinfunction "j11_j11") (pintype "bidirectional"))
      (node (ref "J6") (pin "j14") (pinfunction "j14_j14") (pintype "bidirectional"))
      (node (ref "J6") (pin "j17") (pinfunction "j17_j17") (pintype "bidirectional"))
      (node (ref "J6") (pin "j20") (pinfunction "j20_j20") (pintype "bidirectional"))
      (node (ref "J6") (pin "j23") (pinfunction "j23_j23") (pintype "bidirectional"))
      (node (ref "J6") (pin "j26") (pinfunction "j26_j26") (pintype "bidirectional"))
      (node (ref "J6") (pin "j29") (pinfunction "j29_j29") (pintype "bidirectional"))
      (node (ref "J6") (pin "j32") (pinfunction "j32_j32") (pintype "bidirectional"))
      (node (ref "J6") (pin "j35") (pinfunction "j35_j35") (pintype "bidirectional"))
      (node (ref "J6") (pin "j38") (pinfunction "j38_j38") (pintype "bidirectional"))
      (node (ref "J6") (pin "j4") (pinfunction "j4_j4") (pintype "bidirectional"))
      (node (ref "J6") (pin "j40") (pinfunction "j40_j40") (pintype "bidirectional"))
      (node (ref "J6") (pin "j5") (pinfunction "j5_j5") (pintype "bidirectional"))
      (node (ref "J6") (pin "j8") (pinfunction "j8_j8") (pintype "bidirectional"))
      (node (ref "J6") (pin "k12") (pinfunction "k12_k12") (pintype "bidirectional"))
      (node (ref "J6") (pin "k15") (pinfunction "k15_k15") (pintype "bidirectional"))
      (node (ref "J6") (pin "k18") (pinfunction "k18_k18") (pintype "bidirectional"))
      (node (ref "J6") (pin "k2") (pinfunction "k2_k2") (pintype "bidirectional"))
      (node (ref "J6") (pin "k21") (pinfunction "k21_k21") (pintype "bidirectional"))
      (node (ref "J6") (pin "k24") (pinfunction "k24_k24") (pintype "bidirectional"))
      (node (ref "J6") (pin "k27") (pinfunction "k27_k27") (pintype "bidirectional"))
      (node (ref "J6") (pin "k3") (pinfunction "k3_k3") (pintype "bidirectional"))
      (node (ref "J6") (pin "k30") (pinfunction "k30_k30") (pintype "bidirectional"))
      (node (ref "J6") (pin "k33") (pinfunction "k33_k33") (pintype "bidirectional"))
      (node (ref "J6") (pin "k36") (pinfunction "k36_k36") (pintype "bidirectional"))
      (node (ref "J6") (pin "k39") (pinfunction "k39_k39") (pintype "bidirectional"))
      (node (ref "J6") (pin "k6") (pinfunction "k6_k6") (pintype "bidirectional"))
      (node (ref "J6") (pin "k9") (pinfunction "k9_k9") (pintype "bidirectional"))
    )
    (net (code "183") (name "P3V3") (class "Default")
      (node (ref "J6") (pin "c39") (pinfunction "c39_c39") (pintype "bidirectional"))
      (node (ref "J6") (pin "d36") (pinfunction "d36_d36") (pintype "bidirectional"))
      (node (ref "J6") (pin "d38") (pinfunction "d38_d38") (pintype "bidirectional"))
      (node (ref "J6") (pin "d40") (pinfunction "d40_d40") (pintype "bidirectional"))
      (node (ref "R132") (pin "1") (pinfunction "1_1") (pintype "passive"))
    )
    (net (code "184") (name "P12V0") (class "Default")
      (node (ref "J6") (pin "c35") (pinfunction "c35_c35") (pintype "bidirectional"))
      (node (ref "J6") (pin "c37") (pinfunction "c37_c37") (pintype "bidirectional"))
    )
    (net (code "185") (name "VADJ") (class "Default")
      (node (ref "D3") (pin "1") (pinfunction "C_1") (pintype "passive"))
      (node (ref "D4") (pin "1") (pinfunction "C_1") (pintype "passive"))
      (node (ref "D5") (pin "1") (pinfunction "C_1") (pintype "passive"))
      (node (ref "D6") (pin "1") (pinfunction "C_1") (pintype "passive"))
      (node (ref "J6") (pin "e39") (pinfunction "e39_e39") (pintype "bidirectional"))
      (node (ref "J6") (pin "f40") (pinfunction "f40_f40") (pintype "bidirectional"))
      (node (ref "J6") (pin "g39") (pinfunction "g39_g39") (pintype "bidirectional"))
      (node (ref "J6") (pin "h40") (pinfunction "h40_h40") (pintype "bidirectional"))
    )
    (net (code "186") (name "unconnected-(B2_PANEL-Pad1)") (class "Default")
      (node (ref "B2_PANEL") (pin "1") (pinfunction "1_1") (pintype "bidirectional"))
    )
    (net (code "187") (name "unconnected-(B3_PANEL-Pad1)") (class "Default")
      (node (ref "B3_PANEL") (pin "1") (pinfunction "1_1") (pintype "bidirectional"))
    )
    (net (code "188") (name "unconnected-(J6-Pada2)") (class "Default")
      (node (ref "J6") (pin "a2") (pinfunction "a2_a2") (pintype "bidirectional+no_connect"))
    )
    (net (code "189") (name "unconnected-(J6-Pada3)") (class "Default")
      (node (ref "J6") (pin "a3") (pinfunction "a3_a3") (pintype "bidirectional+no_connect"))
    )
    (net (code "190") (name "unconnected-(J6-Pada6)") (class "Default")
      (node (ref "J6") (pin "a6") (pinfunction "a6_a6") (pintype "bidirectional+no_connect"))
    )
    (net (code "191") (name "unconnected-(J6-Pada7)") (class "Default")
      (node (ref "J6") (pin "a7") (pinfunction "a7_a7") (pintype "bidirectional+no_connect"))
    )
    (net (code "192") (name "unconnected-(J6-Pada10)") (class "Default")
      (node (ref "J6") (pin "a10") (pinfunction "a10_a10") (pintype "bidirectional+no_connect"))
    )
    (net (code "193") (name "unconnected-(J6-Pada11)") (class "Default")
      (node (ref "J6") (pin "a11") (pinfunction "a11_a11") (pintype "bidirectional+no_connect"))
    )
    (net (code "194") (name "unconnected-(J6-Pada14)") (class "Default")
      (node (ref "J6") (pin "a14") (pinfunction "a14_a14") (pintype "bidirectional+no_connect"))
    )
    (net (code "195") (name "unconnected-(J6-Pada15)") (class "Default")
      (node (ref "J6") (pin "a15") (pinfunction "a15_a15") (pintype "bidirectional+no_connect"))
    )
    (net (code "196") (name "unconnected-(J6-Pada18)") (class "Default")
      (node (ref "J6") (pin "a18") (pinfunction "a18_a18") (pintype "bidirectional+no_connect"))
    )
    (net (code "197") (name "unconnected-(J6-Pada19)") (class "Default")
      (node (ref "J6") (pin "a19") (pinfunction "a19_a19") (pintype "bidirectional+no_connect"))
    )
    (net (code "198") (name "unconnected-(J6-Pada22)") (class "Default")
      (node (ref "J6") (pin "a22") (pinfunction "a22_a22") (pintype "bidirectional+no_connect"))
    )
    (net (code "199") (name "unconnected-(J6-Pada23)") (class "Default")
      (node (ref "J6") (pin "a23") (pinfunction "a23_a23") (pintype "bidirectional+no_connect"))
    )
    (net (code "200") (name "unconnected-(J6-Pada26)") (class "Default")
      (node (ref "J6") (pin "a26") (pinfunction "a26_a26") (pintype "bidirectional+no_connect"))
    )
    (net (code "201") (name "unconnected-(J6-Pada27)") (class "Default")
      (node (ref "J6") (pin "a27") (pinfunction "a27_a27") (pintype "bidirectional+no_connect"))
    )
    (net (code "202") (name "unconnected-(J6-Pada30)") (class "Default")
      (node (ref "J6") (pin "a30") (pinfunction "a30_a30") (pintype "bidirectional+no_connect"))
    )
    (net (code "203") (name "unconnected-(J6-Pada31)") (class "Default")
      (node (ref "J6") (pin "a31") (pinfunction "a31_a31") (pintype "bidirectional+no_connect"))
    )
    (net (code "204") (name "unconnected-(J6-Pada34)") (class "Default")
      (node (ref "J6") (pin "a34") (pinfunction "a34_a34") (pintype "bidirectional+no_connect"))
    )
    (net (code "205") (name "unconnected-(J6-Pada35)") (class "Default")
      (node (ref "J6") (pin "a35") (pinfunction "a35_a35") (pintype "bidirectional+no_connect"))
    )
    (net (code "206") (name "unconnected-(J6-Pada38)") (class "Default")
      (node (ref "J6") (pin "a38") (pinfunction "a38_a38") (pintype "bidirectional+no_connect"))
    )
    (net (code "207") (name "unconnected-(J6-Pada39)") (class "Default")
      (node (ref "J6") (pin "a39") (pinfunction "a39_a39") (pintype "bidirectional+no_connect"))
    )
    (net (code "208") (name "unconnected-(J6-Padb4)") (class "Default")
      (node (ref "J6") (pin "b4") (pinfunction "b4_b4") (pintype "bidirectional+no_connect"))
    )
    (net (code "209") (name "unconnected-(J6-Padb5)") (class "Default")
      (node (ref "J6") (pin "b5") (pinfunction "b5_b5") (pintype "bidirectional+no_connect"))
    )
    (net (code "210") (name "unconnected-(J6-Padb8)") (class "Default")
      (node (ref "J6") (pin "b8") (pinfunction "b8_b8") (pintype "bidirectional+no_connect"))
    )
    (net (code "211") (name "unconnected-(J6-Padb9)") (class "Default")
      (node (ref "J6") (pin "b9") (pinfunction "b9_b9") (pintype "bidirectional+no_connect"))
    )
    (net (code "212") (name "unconnected-(J6-Padb12)") (class "Default")
      (node (ref "J6") (pin "b12") (pinfunction "b12_b12") (pintype "bidirectional+no_connect"))
    )
    (net (code "213") (name "unconnected-(J6-Padb13)") (class "Default")
      (node (ref "J6") (pin "b13") (pinfunction "b13_b13") (pintype "bidirectional+no_connect"))
    )
    (net (code "214") (name "unconnected-(J6-Padb16)") (class "Default")
      (node (ref "J6") (pin "b16") (pinfunction "b16_b16") (pintype "bidirectional+no_connect"))
    )
    (net (code "215") (name "unconnected-(J6-Padb17)") (class "Default")
      (node (ref "J6") (pin "b17") (pinfunction "b17_b17") (pintype "bidirectional+no_connect"))
    )
    (net (code "216") (name "unconnected-(J6-Padb20)") (class "Default")
      (node (ref "J6") (pin "b20") (pinfunction "b20_b20") (pintype "bidirectional+no_connect"))
    )
    (net (code "217") (name "unconnected-(J6-Padb21)") (class "Default")
      (node (ref "J6") (pin "b21") (pinfunction "b21_b21") (pintype "bidirectional+no_connect"))
    )
    (net (code "218") (name "unconnected-(J6-Padb24)") (class "Default")
      (node (ref "J6") (pin "b24") (pinfunction "b24_b24") (pintype "bidirectional+no_connect"))
    )
    (net (code "219") (name "unconnected-(J6-Padb25)") (class "Default")
      (node (ref "J6") (pin "b25") (pinfunction "b25_b25") (pintype "bidirectional+no_connect"))
    )
    (net (code "220") (name "unconnected-(J6-Padb28)") (class "Default")
      (node (ref "J6") (pin "b28") (pinfunction "b28_b28") (pintype "bidirectional+no_connect"))
    )
    (net (code "221") (name "unconnected-(J6-Padb29)") (class "Default")
      (node (ref "J6") (pin "b29") (pinfunction "b29_b29") (pintype "bidirectional+no_connect"))
    )
    (net (code "222") (name "unconnected-(J6-Padb32)") (class "Default")
      (node (ref "J6") (pin "b32") (pinfunction "b32_b32") (pintype "bidirectional+no_connect"))
    )
    (net (code "223") (name "unconnected-(J6-Padb33)") (class "Default")
      (node (ref "J6") (pin "b33") (pinfunction "b33_b33") (pintype "bidirectional+no_connect"))
    )
    (net (code "224") (name "unconnected-(J6-Padb36)") (class "Default")
      (node (ref "J6") (pin "b36") (pinfunction "b36_b36") (pintype "bidirectional+no_connect"))
    )
    (net (code "225") (name "unconnected-(J6-Padb37)") (class "Default")
      (node (ref "J6") (pin "b37") (pinfunction "b37_b37") (pintype "bidirectional+no_connect"))
    )
    (net (code "226") (name "unconnected-(J6-Padb40)") (class "Default")
      (node (ref "J6") (pin "b40") (pinfunction "b40_b40") (pintype "bidirectional+no_connect"))
    )
    (net (code "227") (name "unconnected-(J6-Padc2)") (class "Default")
      (node (ref "J6") (pin "c2") (pinfunction "c2_c2") (pintype "bidirectional+no_connect"))
    )
    (net (code "228") (name "unconnected-(J6-Padc3)") (class "Default")
      (node (ref "J6") (pin "c3") (pinfunction "c3_c3") (pintype "bidirectional+no_connect"))
    )
    (net (code "229") (name "unconnected-(J6-Padc6)") (class "Default")
      (node (ref "J6") (pin "c6") (pinfunction "c6_c6") (pintype "bidirectional+no_connect"))
    )
    (net (code "230") (name "unconnected-(J6-Padc7)") (class "Default")
      (node (ref "J6") (pin "c7") (pinfunction "c7_c7") (pintype "bidirectional+no_connect"))
    )
    (net (code "231") (name "unconnected-(J6-Padd1)") (class "Default")
      (node (ref "J6") (pin "d1") (pinfunction "d1_d1") (pintype "bidirectional+no_connect"))
    )
    (net (code "232") (name "unconnected-(J6-Padd4)") (class "Default")
      (node (ref "J6") (pin "d4") (pinfunction "d4_d4") (pintype "bidirectional+no_connect"))
    )
    (net (code "233") (name "unconnected-(J6-Padd5)") (class "Default")
      (node (ref "J6") (pin "d5") (pinfunction "d5_d5") (pintype "bidirectional+no_connect"))
    )
    (net (code "234") (name "unconnected-(J6-Padd29)") (class "Default")
      (node (ref "J6") (pin "d29") (pinfunction "d29_d29") (pintype "bidirectional+no_connect"))
    )
    (net (code "235") (name "unconnected-(J6-Padd33)") (class "Default")
      (node (ref "J6") (pin "d33") (pinfunction "d33_d33") (pintype "bidirectional+no_connect"))
    )
    (net (code "236") (name "unconnected-(J6-Padd34)") (class "Default")
      (node (ref "J6") (pin "d34") (pinfunction "d34_d34") (pintype "bidirectional+no_connect"))
    )
    (net (code "237") (name "unconnected-(J6-Padk1)") (class "Default")
      (node (ref "J6") (pin "k1") (pinfunction "k1_k1") (pintype "bidirectional+no_connect"))
    )
  )
)
